# Versorgung.net
KiCad netlist of a schematic drawn in Altium Designer
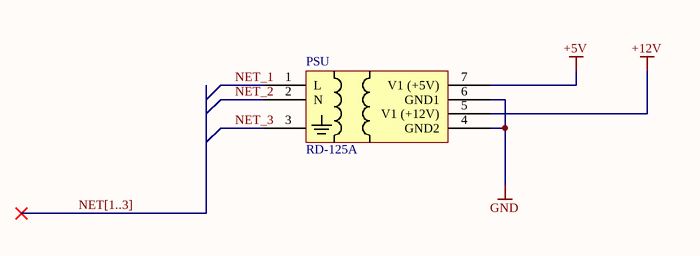
[diagram p0: Versorgung.SchDoc]

(export (version "E")
  (design (tool "Eeschema 10.0.6"))
  (components
    (comp (ref "PSU")
      (value "RD-125A")
      (description "MEAN WELL Schaltnetzteil, 5 V dc, 12 V dc / 7.7A 2-Kanal 130.9W 176 → 264 V ac, 248 → 373 V dc, 88")
      (libsource (lib "3D_Scanner") (part "PSU"))
    )
  )
  (nets
    (net (code "4") (name "+5V") (class "Default")
      (node (ref "PSU") (pin "7") (pinfunction "V1_(+5V)_7") (pintype "power_in"))
    )
    (net (code "5") (name "+12V") (class "Default")
      (node (ref "PSU") (pin "5") (pinfunction "V1_(+12V)_5") (pintype "power_in"))
    )
    (net (code "7") (name "/NET_1") (class "Default")
      (node (ref "PSU") (pin "1") (pinfunction "L_1") (pintype "power_in"))
    )
    (net (code "8") (name "/NET_2") (class "Default")
      (node (ref "PSU") (pin "2") (pinfunction "N_2") (pintype "power_in"))
    )
    (net (code "9") (name "/NET_3") (class "Default") (node (ref "PSU") (pin "3") (pintype "power_in")))
    (net (code "10") (name "GND") (class "Default")
      (node (ref "PSU") (pin "4") (pinfunction "GND2_4") (pintype "power_in"))
      (node (ref "PSU") (pin "6") (pinfunction "GND1_6") (pintype "power_in"))
    )
  )
)
